# PressSensor1.net
KiCad netlist of a schematic drawn in Altium Designer
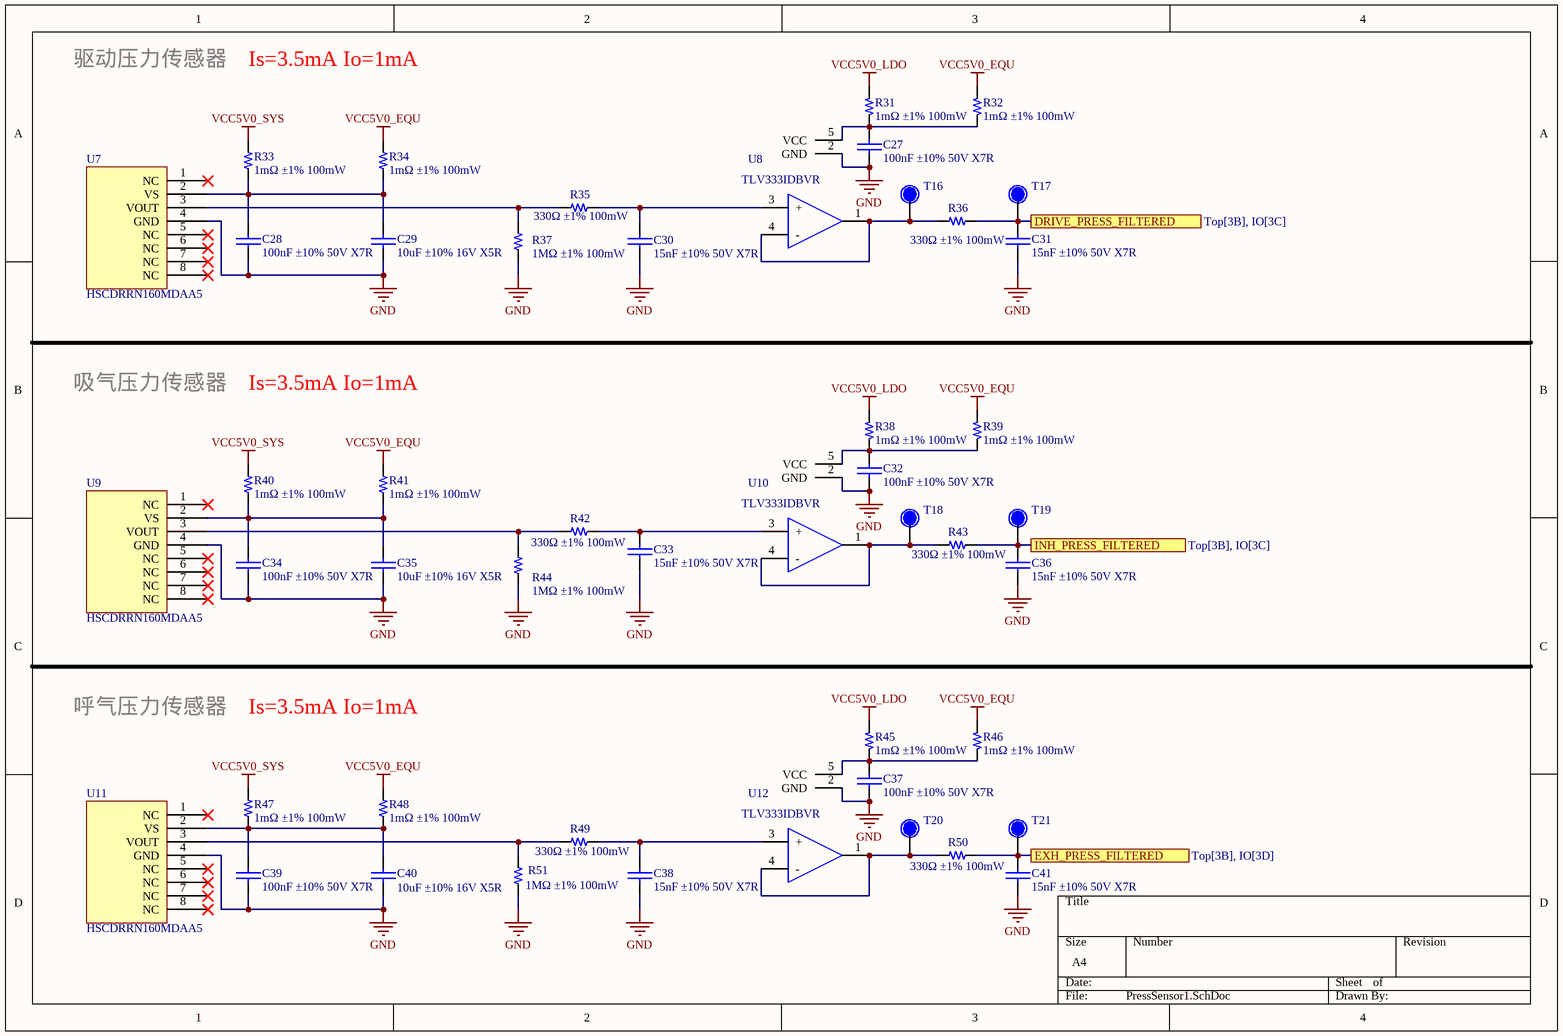
[diagram p0: PressSensor1.SchDoc]

(export (version "E")
  (design (tool "Eeschema 10.0.6"))
  (components
    (comp (ref "C27") (value "100nF ±10% 50V X7R") (footprint "C-0603") (libsource (lib "*") (part "CAP")))
    (comp (ref "C28") (value "100nF ±10% 50V X7R") (footprint "C-0603") (libsource (lib "*") (part "CAP")))
    (comp (ref "C29")
      (value "10uF ±10% 16V X5R")
      (footprint "C-0805")
      (description "Capacitor")
      (libsource (lib "*") (part "CAP"))
    )
    (comp (ref "C30")
      (value "15nF ±10% 50V X7R")
      (footprint "C-0603")
      (description "Capacitor")
      (libsource (lib "*") (part "CAP"))
    )
    (comp (ref "C31")
      (value "15nF ±10% 50V X7R")
      (footprint "C-0603")
      (description "Capacitor")
      (libsource (lib "*") (part "CAP"))
    )
    (comp (ref "C32") (value "100nF ±10% 50V X7R") (footprint "C-0603") (libsource (lib "*") (part "CAP")))
    (comp (ref "C33")
      (value "15nF ±10% 50V X7R")
      (footprint "C-0603")
      (description "Capacitor")
      (libsource (lib "*") (part "CAP"))
    )
    (comp (ref "C34") (value "100nF ±10% 50V X7R") (footprint "C-0603") (libsource (lib "*") (part "CAP")))
    (comp (ref "C35")
      (value "10uF ±10% 16V X5R")
      (footprint "C-0805")
      (description "Capacitor")
      (libsource (lib "*") (part "CAP"))
    )
    (comp (ref "C36")
      (value "15nF ±10% 50V X7R")
      (footprint "C-0603")
      (description "Capacitor")
      (libsource (lib "*") (part "CAP"))
    )
    (comp (ref "C37") (value "100nF ±10% 50V X7R") (footprint "C-0603") (libsource (lib "*") (part "CAP")))
    (comp (ref "C38")
      (value "15nF ±10% 50V X7R")
      (footprint "C-0603")
      (description "Capacitor")
      (libsource (lib "*") (part "CAP"))
    )
    (comp (ref "C39") (value "100nF ±10% 50V X7R") (footprint "C-0603") (libsource (lib "*") (part "CAP")))
    (comp (ref "C40")
      (value "10uF ±10% 16V X5R")
      (footprint "C-0805")
      (description "Capacitor")
      (libsource (lib "*") (part "CAP"))
    )
    (comp (ref "C41")
      (value "15nF ±10% 50V X7R")
      (footprint "C-0603")
      (description "Capacitor")
      (libsource (lib "*") (part "CAP"))
    )
    (comp (ref "R31")
      (value "1mΩ ±1% 100mW")
      (footprint "R-0603")
      (description "国巨\r\n1mΩ ±1% 100mW")
      (libsource (lib "电阻") (part "10K_1"))
    )
    (comp (ref "R32")
      (value "1mΩ ±1% 100mW")
      (footprint "R-0603")
      (description "国巨\r\n1mΩ ±1% 100mW")
      (libsource (lib "电阻") (part "10K_1"))
    )
    (comp (ref "R33")
      (value "1mΩ ±1% 100mW")
      (footprint "R-0603")
      (description "国巨\r\n1mΩ ±1% 100mW")
      (libsource (lib "Device") (part "R-0603"))
    )
    (comp (ref "R34")
      (value "1mΩ ±1% 100mW")
      (footprint "R-0603")
      (description "国巨\r\n1mΩ ±1% 100mW")
      (libsource (lib "Device") (part "R-0603"))
    )
    (comp (ref "R35")
      (value "330Ω ±1% 100mW")
      (footprint "R-0603")
      (libsource (lib "Device") (part "R-0603"))
    )
    (comp (ref "R36")
      (value "330Ω ±1% 100mW")
      (footprint "R-0603")
      (libsource (lib "Device") (part "R-0603"))
    )
    (comp (ref "R37") (value "1MΩ ±1% 100mW") (footprint "R-0603") (libsource (lib "Device") (part "R-0603")))
    (comp (ref "R38")
      (value "1mΩ ±1% 100mW")
      (footprint "R-0603")
      (description "国巨\r\n1mΩ ±1% 100mW")
      (libsource (lib "电阻") (part "10K_1"))
    )
    (comp (ref "R39")
      (value "1mΩ ±1% 100mW")
      (footprint "R-0603")
      (description "国巨\r\n1mΩ ±1% 100mW")
      (libsource (lib "电阻") (part "10K_1"))
    )
    (comp (ref "R40")
      (value "1mΩ ±1% 100mW")
      (footprint "R-0603")
      (description "国巨\r\n1mΩ ±1% 100mW")
      (libsource (lib "Device") (part "R-0603"))
    )
    (comp (ref "R41")
      (value "1mΩ ±1% 100mW")
      (footprint "R-0603")
      (description "国巨\r\n1mΩ ±1% 100mW")
      (libsource (lib "Device") (part "R-0603"))
    )
    (comp (ref "R42")
      (value "330Ω ±1% 100mW")
      (footprint "R-0603")
      (libsource (lib "Device") (part "R-0603"))
    )
    (comp (ref "R43")
      (value "330Ω ±1% 100mW")
      (footprint "R-0603")
      (libsource (lib "Device") (part "R-0603"))
    )
    (comp (ref "R44") (value "1MΩ ±1% 100mW") (footprint "R-0603") (libsource (lib "Device") (part "R-0603")))
    (comp (ref "R45")
      (value "1mΩ ±1% 100mW")
      (footprint "R-0603")
      (description "国巨\r\n1mΩ ±1% 100mW")
      (libsource (lib "电阻") (part "10K_1"))
    )
    (comp (ref "R46")
      (value "1mΩ ±1% 100mW")
      (footprint "R-0603")
      (description "国巨\r\n1mΩ ±1% 100mW")
      (libsource (lib "电阻") (part "10K_1"))
    )
    (comp (ref "R47")
      (value "1mΩ ±1% 100mW")
      (footprint "R-0603")
      (description "国巨\r\n1mΩ ±1% 100mW")
      (libsource (lib "Device") (part "R-0603"))
    )
    (comp (ref "R48")
      (value "1mΩ ±1% 100mW")
      (footprint "R-0603")
      (description "国巨\r\n1mΩ ±1% 100mW")
      (libsource (lib "Device") (part "R-0603"))
    )
    (comp (ref "R49")
      (value "330Ω ±1% 100mW")
      (footprint "R-0603")
      (libsource (lib "Device") (part "R-0603"))
    )
    (comp (ref "R50")
      (value "330Ω ±1% 100mW")
      (footprint "R-0603")
      (libsource (lib "Device") (part "R-0603"))
    )
    (comp (ref "R51") (value "1MΩ ±1% 100mW") (footprint "R-0603") (libsource (lib "Device") (part "R-0603")))
    (comp (ref "T16")
      (value "Test?")
      (footprint "TestPad_SMD")
      (description "TestPad_SMD")
      (libsource (lib "Component") (part "TestPad_SMD"))
    )
    (comp (ref "T17")
      (value "Test?")
      (footprint "TestPad_SMD")
      (description "TestPad_SMD")
      (libsource (lib "Component") (part "TestPad_SMD"))
    )
    (comp (ref "T18")
      (value "Test?")
      (footprint "TestPad_SMD")
      (description "TestPad_SMD")
      (libsource (lib "Component") (part "TestPad_SMD"))
    )
    (comp (ref "T19")
      (value "Test?")
      (footprint "TestPad_SMD")
      (description "TestPad_SMD")
      (libsource (lib "Component") (part "TestPad_SMD"))
    )
    (comp (ref "T20")
      (value "Test?")
      (footprint "TestPad_SMD")
      (description "TestPad_SMD")
      (libsource (lib "Component") (part "TestPad_SMD"))
    )
    (comp (ref "T21")
      (value "Test?")
      (footprint "TestPad_SMD")
      (description "TestPad_SMD")
      (libsource (lib "Component") (part "TestPad_SMD"))
    )
    (comp (ref "U7")
      (value "HSCDRRN160MDAA5")
      (footprint "SSCDRR")
      (libsource (lib "NBP电源板") (part "SSCMJJ010KDAA5"))
    )
    (comp (ref "U8")
      (value "TLV333IDBVR")
      (footprint "SOT23-5")
      (description "品牌：TI，型号：TLV333IDBVR,SOIC-8,–25°~+85°C,单运放，ROHS")
      (libsource (lib "IC") (part "TLV333IDBVR"))
    )
    (comp (ref "U9")
      (value "HSCDRRN160MDAA5")
      (footprint "SSCDRR")
      (libsource (lib "NBP电源板") (part "SSCMJJ010KDAA5"))
    )
    (comp (ref "U10")
      (value "TLV333IDBVR")
      (footprint "SOT23-5")
      (description "品牌：TI，型号：TLV333IDBVR,SOIC-8,–25°~+85°C,单运放，ROHS")
      (libsource (lib "IC") (part "TLV333IDBVR"))
    )
    (comp (ref "U11")
      (value "HSCDRRN160MDAA5")
      (footprint "SSCDRR")
      (libsource (lib "NBP电源板") (part "SSCMJJ010KDAA5"))
    )
    (comp (ref "U12")
      (value "TLV333IDBVR")
      (footprint "SOT23-5")
      (description "品牌：TI，型号：TLV333IDBVR,SOIC-8,–25°~+85°C,单运放，ROHS")
      (libsource (lib "IC") (part "TLV333IDBVR"))
    )
  )
  (nets
    (net (code "1") (name "/DRIVE_PRESS_FILTERED") (class "Default")
      (node (ref "C31") (pin "2") (pinfunction "2_2") (pintype "passive"))
      (node (ref "R36") (pin "1") (pinfunction "1_1") (pintype "passive"))
      (node (ref "T17") (pin "1") (pinfunction "1_1") (pintype "passive"))
    )
    (net (code "2") (name "/EXH_PRESS_FILTERED") (class "Default")
      (node (ref "C41") (pin "2") (pinfunction "2_2") (pintype "passive"))
      (node (ref "R50") (pin "1") (pinfunction "1_1") (pintype "passive"))
      (node (ref "T21") (pin "1") (pinfunction "1_1") (pintype "passive"))
    )
    (net (code "3") (name "/INH_PRESS_FILTERED") (class "Default")
      (node (ref "C36") (pin "2") (pinfunction "2_2") (pintype "passive"))
      (node (ref "R43") (pin "1") (pinfunction "1_1") (pintype "passive"))
      (node (ref "T19") (pin "1") (pinfunction "1_1") (pintype "passive"))
    )
    (net (code "4") (name "GND") (class "Default")
      (node (ref "C27") (pin "1") (pinfunction "1_1") (pintype "passive"))
      (node (ref "C28") (pin "1") (pinfunction "1_1") (pintype "passive"))
      (node (ref "C29") (pin "1") (pinfunction "1_1") (pintype "passive"))
      (node (ref "C30") (pin "1") (pinfunction "1_1") (pintype "passive"))
      (node (ref "C31") (pin "1") (pinfunction "1_1") (pintype "passive"))
      (node (ref "C32") (pin "1") (pinfunction "1_1") (pintype "passive"))
      (node (ref "C33") (pin "1") (pinfunction "1_1") (pintype "passive"))
      (node (ref "C34") (pin "1") (pinfunction "1_1") (pintype "passive"))
      (node (ref "C35") (pin "1") (pinfunction "1_1") (pintype "passive"))
      (node (ref "C36") (pin "1") (pinfunction "1_1") (pintype "passive"))
      (node (ref "C37") (pin "1") (pinfunction "1_1") (pintype "passive"))
      (node (ref "C38") (pin "1") (pinfunction "1_1") (pintype "passive"))
      (node (ref "C39") (pin "1") (pinfunction "1_1") (pintype "passive"))
      (node (ref "C40") (pin "1") (pinfunction "1_1") (pintype "passive"))
      (node (ref "C41") (pin "1") (pinfunction "1_1") (pintype "passive"))
      (node (ref "R37") (pin "2") (pinfunction "2_2") (pintype "passive"))
      (node (ref "R44") (pin "2") (pinfunction "2_2") (pintype "passive"))
      (node (ref "R51") (pin "2") (pinfunction "2_2") (pintype "passive"))
      (node (ref "U10") (pin "2") (pinfunction "GND_2") (pintype "passive"))
      (node (ref "U11") (pin "4") (pinfunction "GND_4") (pintype "passive"))
      (node (ref "U12") (pin "2") (pinfunction "GND_2") (pintype "passive"))
      (node (ref "U7") (pin "4") (pinfunction "GND_4") (pintype "passive"))
      (node (ref "U8") (pin "2") (pinfunction "GND_2") (pintype "passive"))
      (node (ref "U9") (pin "4") (pinfunction "GND_4") (pintype "passive"))
    )
    (net (code "5") (name "Net-(R31-TOP)") (class "Default")
      (node (ref "C27") (pin "2") (pinfunction "2_2") (pintype "passive"))
      (node (ref "R31") (pin "1") (pinfunction "TOP_1") (pintype "passive"))
      (node (ref "R32") (pin "1") (pinfunction "TOP_1") (pintype "passive"))
      (node (ref "U8") (pin "5") (pinfunction "VCC_5") (pintype "passive"))
    )
    (net (code "6") (name "Net-(R38-TOP)") (class "Default")
      (node (ref "C32") (pin "2") (pinfunction "2_2") (pintype "passive"))
      (node (ref "R38") (pin "1") (pinfunction "TOP_1") (pintype "passive"))
      (node (ref "R39") (pin "1") (pinfunction "TOP_1") (pintype "passive"))
      (node (ref "U10") (pin "5") (pinfunction "VCC_5") (pintype "passive"))
    )
    (net (code "7") (name "Net-(R45-TOP)") (class "Default")
      (node (ref "C37") (pin "2") (pinfunction "2_2") (pintype "passive"))
      (node (ref "R45") (pin "1") (pinfunction "TOP_1") (pintype "passive"))
      (node (ref "R46") (pin "1") (pinfunction "TOP_1") (pintype "passive"))
      (node (ref "U12") (pin "5") (pinfunction "VCC_5") (pintype "passive"))
    )
    (net (code "8") (name "Net-(U7-VOUT)") (class "Default")
      (node (ref "R35") (pin "2") (pinfunction "2_2") (pintype "passive"))
      (node (ref "R37") (pin "1") (pinfunction "1_1") (pintype "passive"))
      (node (ref "U7") (pin "3") (pinfunction "VOUT_3") (pintype "passive"))
    )
    (net (code "9") (name "Net-(U7-VS)") (class "Default")
      (node (ref "C28") (pin "2") (pinfunction "2_2") (pintype "passive"))
      (node (ref "C29") (pin "2") (pinfunction "2_2") (pintype "passive"))
      (node (ref "R33") (pin "2") (pinfunction "2_2") (pintype "passive"))
      (node (ref "R34") (pin "2") (pinfunction "2_2") (pintype "passive"))
      (node (ref "U7") (pin "2") (pinfunction "VS_2") (pintype "passive"))
    )
    (net (code "10") (name "Net-(U8-+)") (class "Default")
      (node (ref "C30") (pin "2") (pinfunction "2_2") (pintype "passive"))
      (node (ref "R35") (pin "1") (pinfunction "1_1") (pintype "passive"))
      (node (ref "U8") (pin "3") (pinfunction "+_3") (pintype "passive"))
    )
    (net (code "11") (name "Net-(U8--)") (class "Default")
      (node (ref "R36") (pin "2") (pinfunction "2_2") (pintype "passive"))
      (node (ref "T16") (pin "1") (pinfunction "1_1") (pintype "passive"))
      (node (ref "U8") (pin "1") (pintype "passive"))
      (node (ref "U8") (pin "4") (pinfunction "-_4") (pintype "passive"))
    )
    (net (code "12") (name "Net-(U9-VOUT)") (class "Default")
      (node (ref "R42") (pin "2") (pinfunction "2_2") (pintype "passive"))
      (node (ref "R44") (pin "1") (pinfunction "1_1") (pintype "passive"))
      (node (ref "U9") (pin "3") (pinfunction "VOUT_3") (pintype "passive"))
    )
    (net (code "13") (name "Net-(U9-VS)") (class "Default")
      (node (ref "C34") (pin "2") (pinfunction "2_2") (pintype "passive"))
      (node (ref "C35") (pin "2") (pinfunction "2_2") (pintype "passive"))
      (node (ref "R40") (pin "2") (pinfunction "2_2") (pintype "passive"))
      (node (ref "R41") (pin "2") (pinfunction "2_2") (pintype "passive"))
      (node (ref "U9") (pin "2") (pinfunction "VS_2") (pintype "passive"))
    )
    (net (code "14") (name "Net-(U10-+)") (class "Default")
      (node (ref "C33") (pin "2") (pinfunction "2_2") (pintype "passive"))
      (node (ref "R42") (pin "1") (pinfunction "1_1") (pintype "passive"))
      (node (ref "U10") (pin "3") (pinfunction "+_3") (pintype "passive"))
    )
    (net (code "15") (name "Net-(U10--)") (class "Default")
      (node (ref "R43") (pin "2") (pinfunction "2_2") (pintype "passive"))
      (node (ref "T18") (pin "1") (pinfunction "1_1") (pintype "passive"))
      (node (ref "U10") (pin "1") (pintype "passive"))
      (node (ref "U10") (pin "4") (pinfunction "-_4") (pintype "passive"))
    )
    (net (code "16") (name "Net-(U11-VOUT)") (class "Default")
      (node (ref "R49") (pin "2") (pinfunction "2_2") (pintype "passive"))
      (node (ref "R51") (pin "1") (pinfunction "1_1") (pintype "passive"))
      (node (ref "U11") (pin "3") (pinfunction "VOUT_3") (pintype "passive"))
    )
    (net (code "17") (name "Net-(U11-VS)") (class "Default")
      (node (ref "C39") (pin "2") (pinfunction "2_2") (pintype "passive"))
      (node (ref "C40") (pin "2") (pinfunction "2_2") (pintype "passive"))
      (node (ref "R47") (pin "2") (pinfunction "2_2") (pintype "passive"))
      (node (ref "R48") (pin "2") (pinfunction "2_2") (pintype "passive"))
      (node (ref "U11") (pin "2") (pinfunction "VS_2") (pintype "passive"))
    )
    (net (code "18") (name "Net-(U12-+)") (class "Default")
      (node (ref "C38") (pin "2") (pinfunction "2_2") (pintype "passive"))
      (node (ref "R49") (pin "1") (pinfunction "1_1") (pintype "passive"))
      (node (ref "U12") (pin "3") (pinfunction "+_3") (pintype "passive"))
    )
    (net (code "19") (name "Net-(U12--)") (class "Default")
      (node (ref "R50") (pin "2") (pinfunction "2_2") (pintype "passive"))
      (node (ref "T20") (pin "1") (pinfunction "1_1") (pintype "passive"))
      (node (ref "U12") (pin "1") (pintype "passive"))
      (node (ref "U12") (pin "4") (pinfunction "-_4") (pintype "passive"))
    )
    (net (code "20") (name "VCC5V0_EQU") (class "Default")
      (node (ref "R32") (pin "2") (pinfunction "BOT_2") (pintype "passive"))
      (node (ref "R34") (pin "1") (pinfunction "1_1") (pintype "passive"))
      (node (ref "R39") (pin "2") (pinfunction "BOT_2") (pintype "passive"))
      (node (ref "R41") (pin "1") (pinfunction "1_1") (pintype "passive"))
      (node (ref "R46") (pin "2") (pinfunction "BOT_2") (pintype "passive"))
      (node (ref "R48") (pin "1") (pinfunction "1_1") (pintype "passive"))
    )
    (net (code "21") (name "VCC5V0_LDO") (class "Default")
      (node (ref "R31") (pin "2") (pinfunction "BOT_2") (pintype "passive"))
      (node (ref "R38") (pin "2") (pinfunction "BOT_2") (pintype "passive"))
      (node (ref "R45") (pin "2") (pinfunction "BOT_2") (pintype "passive"))
    )
    (net (code "22") (name "VCC5V0_SYS") (class "Default")
      (node (ref "R33") (pin "1") (pinfunction "1_1") (pintype "passive"))
      (node (ref "R40") (pin "1") (pinfunction "1_1") (pintype "passive"))
      (node (ref "R47") (pin "1") (pinfunction "1_1") (pintype "passive"))
    )
    (net (code "23") (name "unconnected-(U7-NC-Pad1)") (class "Default")
      (node (ref "U7") (pin "1") (pinfunction "NC_1") (pintype "passive+no_connect"))
    )
    (net (code "24") (name "unconnected-(U7-NC-Pad5)") (class "Default")
      (node (ref "U7") (pin "5") (pinfunction "NC_5") (pintype "passive+no_connect"))
    )
    (net (code "25") (name "unconnected-(U7-NC-Pad6)") (class "Default")
      (node (ref "U7") (pin "6") (pinfunction "NC_6") (pintype "passive+no_connect"))
    )
    (net (code "26") (name "unconnected-(U7-NC-Pad7)") (class "Default")
      (node (ref "U7") (pin "7") (pinfunction "NC_7") (pintype "passive+no_connect"))
    )
    (net (code "27") (name "unconnected-(U7-NC-Pad8)") (class "Default")
      (node (ref "U7") (pin "8") (pinfunction "NC_8") (pintype "passive+no_connect"))
    )
    (net (code "28") (name "unconnected-(U9-NC-Pad1)") (class "Default")
      (node (ref "U9") (pin "1") (pinfunction "NC_1") (pintype "passive+no_connect"))
    )
    (net (code "29") (name "unconnected-(U9-NC-Pad5)") (class "Default")
      (node (ref "U9") (pin "5") (pinfunction "NC_5") (pintype "passive+no_connect"))
    )
    (net (code "30") (name "unconnected-(U9-NC-Pad6)") (class "Default")
      (node (ref "U9") (pin "6") (pinfunction "NC_6") (pintype "passive+no_connect"))
    )
    (net (code "31") (name "unconnected-(U9-NC-Pad7)") (class "Default")
      (node (ref "U9") (pin "7") (pinfunction "NC_7") (pintype "passive+no_connect"))
    )
    (net (code "32") (name "unconnected-(U9-NC-Pad8)") (class "Default")
      (node (ref "U9") (pin "8") (pinfunction "NC_8") (pintype "passive+no_connect"))
    )
    (net (code "33") (name "unconnected-(U11-NC-Pad1)") (class "Default")
      (node (ref "U11") (pin "1") (pinfunction "NC_1") (pintype "passive+no_connect"))
    )
    (net (code "34") (name "unconnected-(U11-NC-Pad5)") (class "Default")
      (node (ref "U11") (pin "5") (pinfunction "NC_5") (pintype "passive+no_connect"))
    )
    (net (code "35") (name "unconnected-(U11-NC-Pad6)") (class "Default")
      (node (ref "U11") (pin "6") (pinfunction "NC_6") (pintype "passive+no_connect"))
    )
    (net (code "36") (name "unconnected-(U11-NC-Pad7)") (class "Default")
      (node (ref "U11") (pin "7") (pinfunction "NC_7") (pintype "passive+no_connect"))
    )
    (net (code "37") (name "unconnected-(U11-NC-Pad8)") (class "Default")
      (node (ref "U11") (pin "8") (pinfunction "NC_8") (pintype "passive+no_connect"))
    )
  )
)
